# remora-2.net
KiCad netlist of a schematic drawn in Altium Designer
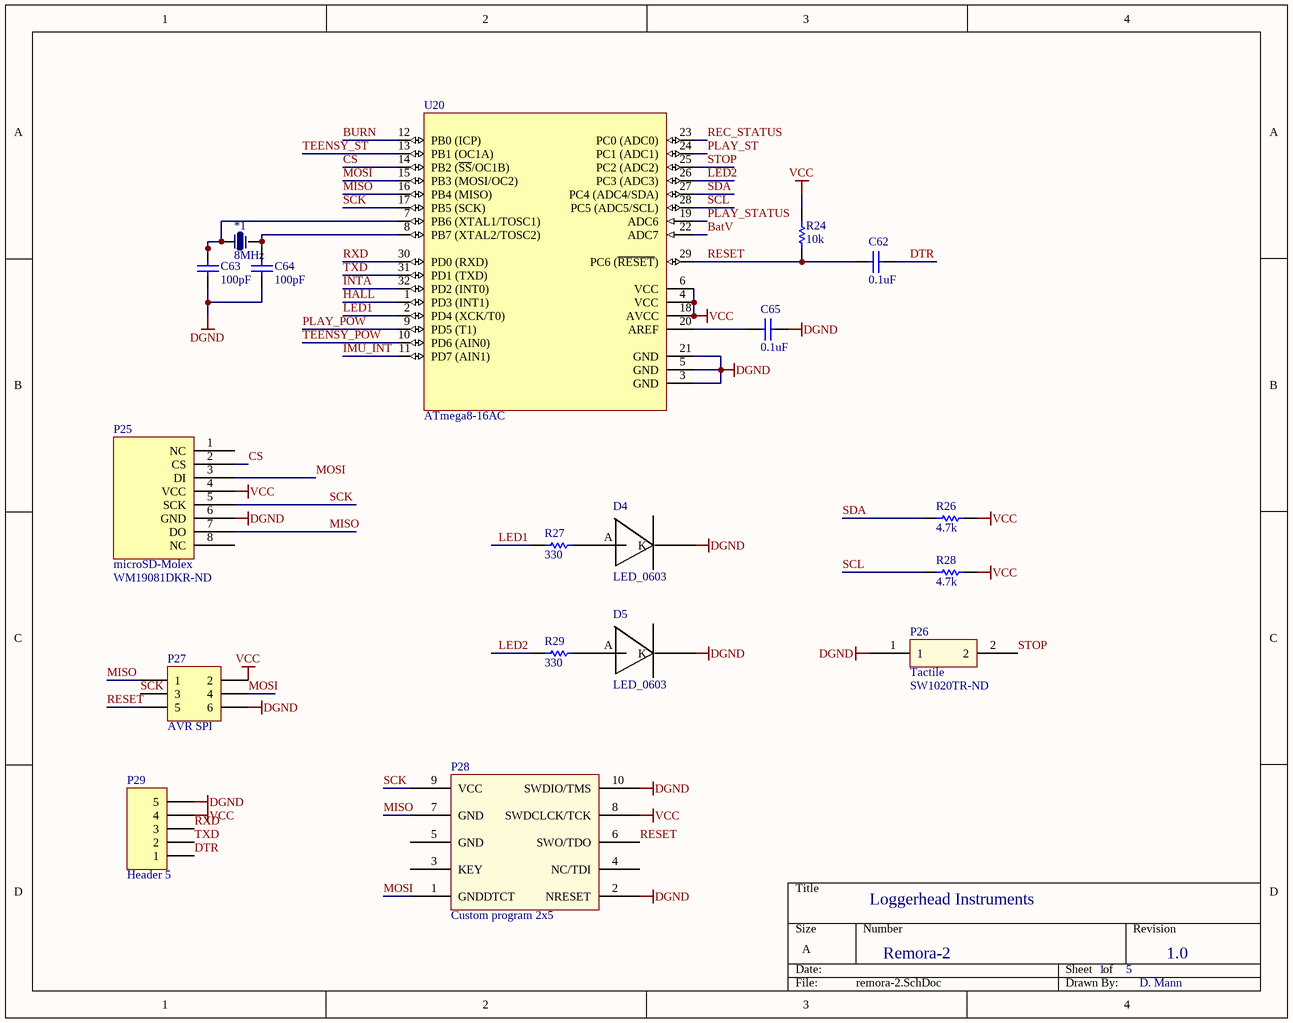
[diagram p0: remora-2.SchDoc]

(export (version "E")
  (design (tool "Eeschema 10.0.6"))
  (components
    (comp (ref "*1") (value "8MHz") (footprint "XTAL-ABM3") (libsource (lib "Loggerhead") (part "XTAL-ABM3")))
    (comp (ref "C62")
      (value "0.1uF")
      (footprint "0402")
      (description "Ceramic Chip Capacitor - Standard")
      (fields (field (name "PUBLISHER") "Altium Limited"))
      (libsource (lib "KEMET Chip Capacitor") (part "C0402"))
    )
    (comp (ref "C63")
      (value "100pF")
      (footprint "0402")
      (description "Ceramic Chip Capacitor - Standard")
      (fields (field (name "PUBLISHER") "Altium Limited"))
      (libsource (lib "KEMET Chip Capacitor") (part "C0402"))
    )
    (comp (ref "C64")
      (value "100pF")
      (footprint "0402")
      (description "Ceramic Chip Capacitor - Standard")
      (fields (field (name "PUBLISHER") "Altium Limited"))
      (libsource (lib "KEMET Chip Capacitor") (part "C0402"))
    )
    (comp (ref "C65")
      (value "0.1uF")
      (footprint "0402")
      (description "Ceramic Chip Capacitor - Standard")
      (fields (field (name "PUBLISHER") "Altium Limited"))
      (libsource (lib "KEMET Chip Capacitor") (part "C0402"))
    )
    (comp (ref "D4")
      (value "LED_0603")
      (footprint "Diode0603")
      (libsource (lib "Loggerhead") (part "LED_0603"))
    )
    (comp (ref "D5")
      (value "LED_0603")
      (footprint "Diode0603")
      (libsource (lib "Loggerhead") (part "LED_0603"))
    )
    (comp (ref "P25")
      (value "microSD-Molex")
      (footprint "microSD_Molex_hinged")
      (fields (field (name "SUPPLIER PART NUMBER 1") "WM19081DKR-ND"))
      (libsource (lib "Loggerhead") (part "microSD_Molex_hinged"))
    )
    (comp (ref "P26")
      (value "Tactile")
      (footprint "Tactile-B3U-1000")
      (fields (field (name "SUPPLIER PART NUMBER 1") "SW1020TR-ND"))
      (libsource (lib "Loggerhead") (part "Tactile_B3U-1000"))
    )
    (comp (ref "P27")
      (value "AVR SPI")
      (footprint "HDR2X3")
      (description "Header, 3-Pin, Dual row")
      (fields (field (name "PUBLISHER") "Altium Limited"))
      (libsource (lib "Miscellaneous Connectors") (part "Header 3X2"))
    )
    (comp (ref "P28")
      (value "Custom program 2x5")
      (footprint "Header_2x5_50mil")
      (libsource (lib "Loggerhead") (part "CortexDebug"))
    )
    (comp (ref "P29")
      (value "Header 5")
      (footprint "HDR1X5")
      (description "Header, 5-Pin")
      (fields (field (name "PUBLISHER") "Altium Limited"))
      (libsource (lib "Miscellaneous Connectors") (part "Header 5"))
    )
    (comp (ref "R24")
      (value "10k")
      (footprint "3-0603")
      (fields (field (name "PUBLISHER") "Altium Limited"))
      (libsource (lib "Panasonic Resistor") (part "ERJ3RK"))
    )
    (comp (ref "R26")
      (value "4.7k")
      (footprint "3-0603")
      (fields (field (name "PUBLISHER") "Altium Limited"))
      (libsource (lib "Panasonic Resistor") (part "ERJ3RK"))
    )
    (comp (ref "R27")
      (value "330")
      (footprint "3-0603")
      (fields (field (name "PUBLISHER") "Altium Limited"))
      (libsource (lib "Panasonic Resistor") (part "ERJ3RK"))
    )
    (comp (ref "R28")
      (value "4.7k")
      (footprint "3-0603")
      (fields (field (name "PUBLISHER") "Altium Limited"))
      (libsource (lib "Panasonic Resistor") (part "ERJ3RK"))
    )
    (comp (ref "R29")
      (value "330")
      (footprint "3-0603")
      (fields (field (name "PUBLISHER") "Altium Limited"))
      (libsource (lib "Panasonic Resistor") (part "ERJ3RK"))
    )
    (comp (ref "U20")
      (value "ATmega8-16AC")
      (footprint "32M1-A_M")
      (description "8-Bit AVR Microcontroller with 8K Bytes of In-System Programmable Flash Memory")
      (fields (field (name "PUBLISHER") "Altium Limited"))
      (libsource (lib "Atmel Microcontroller 8-Bit AVR") (part "ATmega8-16AC"))
    )
  )
  (nets
    (net (code "1") (name "/BURN") (class "Default")
      (node (ref "U20") (pin "12") (pinfunction "PB0_(ICP)_12") (pintype "bidirectional"))
    )
    (net (code "2") (name "/BatV") (class "Default")
      (node (ref "U20") (pin "22") (pinfunction "ADC7_22") (pintype "input"))
    )
    (net (code "3") (name "/CS") (class "Default")
      (node (ref "P25") (pin "2") (pinfunction "CS_2") (pintype "passive"))
      (node (ref "U20") (pin "14") (pinfunction "PB2_(~{SS}/OC1B)_14") (pintype "bidirectional"))
    )
    (net (code "4") (name "/DTR") (class "Default")
      (node (ref "C62") (pin "2") (pinfunction "2_2") (pintype "passive"))
      (node (ref "P29") (pin "1") (pinfunction "1_1") (pintype "passive"))
    )
    (net (code "5") (name "/HALL") (class "Default")
      (node (ref "U20") (pin "1") (pinfunction "PD3_(INT1)_1") (pintype "bidirectional"))
    )
    (net (code "6") (name "/IMU_INT") (class "Default")
      (node (ref "U20") (pin "11") (pinfunction "PD7_(AIN1)_11") (pintype "bidirectional"))
    )
    (net (code "7") (name "/INTA") (class "Default")
      (node (ref "U20") (pin "32") (pinfunction "PD2_(INT0)_32") (pintype "bidirectional"))
    )
    (net (code "8") (name "/LED1") (class "Default")
      (node (ref "R27") (pin "1") (pinfunction "1_1") (pintype "passive"))
      (node (ref "U20") (pin "2") (pinfunction "PD4_(XCK/T0)_2") (pintype "bidirectional"))
    )
    (net (code "9") (name "/LED2") (class "Default")
      (node (ref "R29") (pin "1") (pinfunction "1_1") (pintype "passive"))
      (node (ref "U20") (pin "26") (pinfunction "PC3_(ADC3)_26") (pintype "bidirectional"))
    )
    (net (code "10") (name "/MISO") (class "Default")
      (node (ref "P25") (pin "7") (pinfunction "DO_7") (pintype "passive"))
      (node (ref "P27") (pin "1") (pinfunction "1_1") (pintype "passive"))
      (node (ref "P28") (pin "7") (pinfunction "GND_7") (pintype "passive"))
      (node (ref "U20") (pin "16") (pinfunction "PB4_(MISO)_16") (pintype "bidirectional"))
    )
    (net (code "11") (name "/MOSI") (class "Default")
      (node (ref "P25") (pin "3") (pinfunction "DI_3") (pintype "passive"))
      (node (ref "P27") (pin "4") (pinfunction "4_4") (pintype "passive"))
      (node (ref "P28") (pin "1") (pinfunction "GNDDTCT_1") (pintype "passive"))
      (node (ref "U20") (pin "15") (pinfunction "PB3_(MOSI/OC2)_15") (pintype "bidirectional"))
    )
    (net (code "12") (name "/PLAY_POW") (class "Default")
      (node (ref "U20") (pin "9") (pinfunction "PD5_(T1)_9") (pintype "bidirectional"))
    )
    (net (code "13") (name "/PLAY_ST") (class "Default")
      (node (ref "U20") (pin "24") (pinfunction "PC1_(ADC1)_24") (pintype "bidirectional"))
    )
    (net (code "14") (name "/PLAY_STATUS") (class "Default")
      (node (ref "U20") (pin "19") (pinfunction "ADC6_19") (pintype "input"))
    )
    (net (code "15") (name "/REC_STATUS") (class "Default")
      (node (ref "U20") (pin "23") (pinfunction "PC0_(ADC0)_23") (pintype "bidirectional"))
    )
    (net (code "16") (name "/RESET") (class "Default")
      (node (ref "C62") (pin "1") (pinfunction "1_1") (pintype "passive"))
      (node (ref "P27") (pin "5") (pinfunction "5_5") (pintype "passive"))
      (node (ref "P28") (pin "6") (pinfunction "SWO/TDO_6") (pintype "passive"))
      (node (ref "R24") (pin "1") (pinfunction "1_1") (pintype "passive"))
      (node (ref "U20") (pin "29") (pinfunction "PC6_(~{RESET})_29") (pintype "bidirectional"))
    )
    (net (code "17") (name "/RXD") (class "Default")
      (node (ref "P29") (pin "3") (pinfunction "3_3") (pintype "passive"))
      (node (ref "U20") (pin "30") (pinfunction "PD0_(RXD)_30") (pintype "bidirectional"))
    )
    (net (code "18") (name "/SCK") (class "Default")
      (node (ref "P25") (pin "5") (pinfunction "SCK_5") (pintype "passive"))
      (node (ref "P27") (pin "3") (pinfunction "3_3") (pintype "passive"))
      (node (ref "P28") (pin "9") (pinfunction "VCC_9") (pintype "passive"))
      (node (ref "U20") (pin "17") (pinfunction "PB5_(SCK)_17") (pintype "bidirectional"))
    )
    (net (code "19") (name "/SCL") (class "Default")
      (node (ref "R28") (pin "1") (pinfunction "1_1") (pintype "passive"))
      (node (ref "U20") (pin "28") (pinfunction "PC5_(ADC5/SCL)_28") (pintype "bidirectional"))
    )
    (net (code "20") (name "/SDA") (class "Default")
      (node (ref "R26") (pin "1") (pinfunction "1_1") (pintype "passive"))
      (node (ref "U20") (pin "27") (pinfunction "PC4_(ADC4/SDA)_27") (pintype "bidirectional"))
    )
    (net (code "21") (name "/STOP") (class "Default")
      (node (ref "P26") (pin "2") (pinfunction "2_2") (pintype "passive"))
      (node (ref "U20") (pin "25") (pinfunction "PC2_(ADC2)_25") (pintype "bidirectional"))
    )
    (net (code "22") (name "/TEENSY_POW") (class "Default")
      (node (ref "U20") (pin "10") (pinfunction "PD6_(AIN0)_10") (pintype "bidirectional"))
    )
    (net (code "23") (name "/TEENSY_ST") (class "Default")
      (node (ref "U20") (pin "13") (pinfunction "PB1_(OC1A)_13") (pintype "bidirectional"))
    )
    (net (code "24") (name "/TXD") (class "Default")
      (node (ref "P29") (pin "2") (pinfunction "2_2") (pintype "passive"))
      (node (ref "U20") (pin "31") (pinfunction "PD1_(TXD)_31") (pintype "bidirectional"))
    )
    (net (code "25") (name "DGND") (class "Default")
      (node (ref "C63") (pin "1") (pinfunction "1_1") (pintype "passive"))
      (node (ref "C64") (pin "1") (pinfunction "1_1") (pintype "passive"))
      (node (ref "C65") (pin "2") (pinfunction "2_2") (pintype "passive"))
      (node (ref "D4") (pin "K") (pinfunction "K_K") (pintype "passive"))
      (node (ref "D5") (pin "K") (pinfunction "K_K") (pintype "passive"))
      (node (ref "P25") (pin "6") (pinfunction "GND_6") (pintype "passive"))
      (node (ref "P26") (pin "1") (pinfunction "1_1") (pintype "passive"))
      (node (ref "P27") (pin "6") (pinfunction "6_6") (pintype "passive"))
      (node (ref "P28") (pin "10") (pinfunction "SWDIO/TMS_10") (pintype "passive"))
      (node (ref "P28") (pin "2") (pinfunction "NRESET_2") (pintype "passive"))
      (node (ref "P29") (pin "5") (pinfunction "5_5") (pintype "passive"))
      (node (ref "U20") (pin "21") (pinfunction "GND_21") (pintype "power_in"))
      (node (ref "U20") (pin "3") (pinfunction "GND_3") (pintype "power_in"))
      (node (ref "U20") (pin "5") (pinfunction "GND_5") (pintype "power_in"))
    )
    (net (code "26") (name "Net-(D4-PadA)") (class "Default")
      (node (ref "D4") (pin "A") (pinfunction "A_A") (pintype "passive"))
      (node (ref "R27") (pin "2") (pinfunction "2_2") (pintype "passive"))
    )
    (net (code "27") (name "Net-(D5-PadA)") (class "Default")
      (node (ref "D5") (pin "A") (pinfunction "A_A") (pintype "passive"))
      (node (ref "R29") (pin "2") (pinfunction "2_2") (pintype "passive"))
    )
    (net (code "28") (name "Net-(U20-AREF)") (class "Default")
      (node (ref "C65") (pin "1") (pinfunction "1_1") (pintype "passive"))
      (node (ref "U20") (pin "20") (pinfunction "AREF_20") (pintype "passive"))
    )
    (net (code "29") (name "Net-(U20-PB6_(XTAL1{slash}TOSC1))") (class "Default")
      (node (ref "*1") (pin "1") (pinfunction "1_1") (pintype "passive"))
      (node (ref "C63") (pin "2") (pinfunction "2_2") (pintype "passive"))
      (node (ref "U20") (pin "7") (pinfunction "PB6_(XTAL1/TOSC1)_7") (pintype "bidirectional"))
    )
    (net (code "30") (name "Net-(U20-PB7_(XTAL2{slash}TOSC2))") (class "Default")
      (node (ref "*1") (pin "2") (pinfunction "2_2") (pintype "passive"))
      (node (ref "C64") (pin "2") (pinfunction "2_2") (pintype "passive"))
      (node (ref "U20") (pin "8") (pinfunction "PB7_(XTAL2/TOSC2)_8") (pintype "bidirectional"))
    )
    (net (code "31") (name "VCC") (class "Default")
      (node (ref "P25") (pin "4") (pinfunction "VCC_4") (pintype "passive"))
      (node (ref "P27") (pin "2") (pinfunction "2_2") (pintype "passive"))
      (node (ref "P28") (pin "8") (pinfunction "SWDCLCK/TCK_8") (pintype "passive"))
      (node (ref "P29") (pin "4") (pinfunction "4_4") (pintype "passive"))
      (node (ref "R24") (pin "2") (pinfunction "2_2") (pintype "passive"))
      (node (ref "R26") (pin "2") (pinfunction "2_2") (pintype "passive"))
      (node (ref "R28") (pin "2") (pinfunction "2_2") (pintype "passive"))
      (node (ref "U20") (pin "18") (pinfunction "AVCC_18") (pintype "power_in"))
      (node (ref "U20") (pin "4") (pinfunction "VCC_4") (pintype "power_in"))
      (node (ref "U20") (pin "6") (pinfunction "VCC_6") (pintype "power_in"))
    )
    (net (code "32") (name "unconnected-(P25-NC-Pad1)") (class "Default")
      (node (ref "P25") (pin "1") (pinfunction "NC_1") (pintype "passive"))
    )
    (net (code "33") (name "unconnected-(P25-NC-Pad8)") (class "Default")
      (node (ref "P25") (pin "8") (pinfunction "NC_8") (pintype "passive"))
    )
    (net (code "34") (name "unconnected-(P28-GND-Pad5)") (class "Default")
      (node (ref "P28") (pin "5") (pinfunction "GND_5") (pintype "passive"))
    )
    (net (code "35") (name "unconnected-(P28-KEY-Pad3)") (class "Default")
      (node (ref "P28") (pin "3") (pinfunction "KEY_3") (pintype "passive"))
    )
    (net (code "36") (name "unconnected-(P28-NC{slash}TDI-Pad4)") (class "Default")
      (node (ref "P28") (pin "4") (pinfunction "NC/TDI_4") (pintype "passive"))
    )
  )
)
